# BuckModuleTest.net
KiCad netlist of a schematic drawn in EAGLE
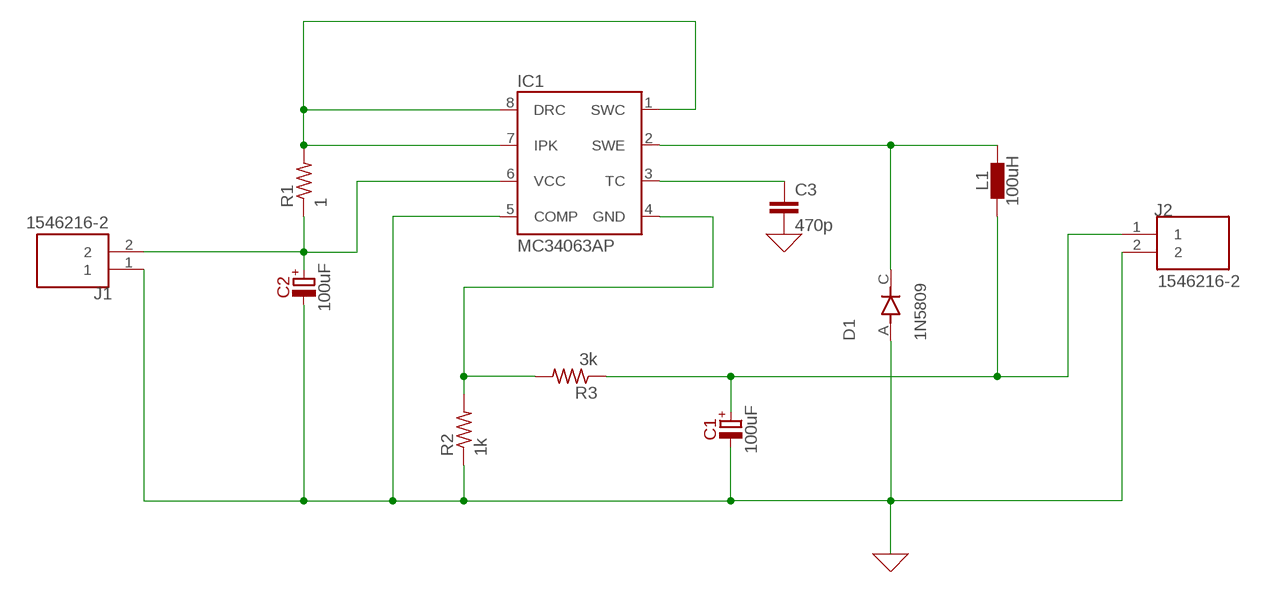
[diagram p0: schematic, sheet 1]

(export (version "E")
  (design (tool "Eeschema 10.0.6"))
  (components
    (comp (ref "C1")
      (value "100uF")
      (footprint "eagle-import:E1,5-4")
      (libsource (lib "eagle-import") (part "?1U/50V"))
    )
    (comp (ref "C2")
      (value "100uF")
      (footprint "eagle-import:E1,5-4")
      (libsource (lib "eagle-import") (part "?1U/50V"))
    )
    (comp (ref "C3")
      (value "470p")
      (footprint "eagle-import:C2.5-2")
      (libsource (lib "eagle-import") (part "C2.5/2"))
    )
    (comp (ref "D1")
      (value "1N5809")
      (footprint "eagle-import:DIOAD1060W80L520D270")
      (fields (field (name "MF") "ON Semiconductor") (field (name "MP") "1N4007"))
      (libsource (lib "eagle-import") (part "1N4007"))
    )
    (comp (ref "IC1")
      (value "MC34063AP")
      (footprint "eagle-import:DIL-08")
      (fields (field (name "MF") "Texas Instruments") (field (name "MP") "MC34063A"))
      (libsource (lib "eagle-import") (part "MC34063AP"))
    )
    (comp (ref "J1")
      (value "1546216-2")
      (footprint "eagle-import:TE_1546216-2")
      (fields (field (name "MF") "TE Connectivity"))
      (libsource (lib "eagle-import") (part "1546216-2"))
    )
    (comp (ref "J2")
      (value "1546216-2")
      (footprint "eagle-import:TE_1546216-2")
      (fields (field (name "MF") "TE Connectivity"))
      (libsource (lib "eagle-import") (part "1546216-2"))
    )
    (comp (ref "L1")
      (value "100uH")
      (footprint "eagle-import:L_NR80XX")
      (libsource (lib "eagle-import") (part "INDUCTOR-NR80XX"))
    )
    (comp (ref "R1")
      (value "1")
      (footprint "eagle-import:0207_12")
      (libsource (lib "eagle-import") (part "R-US_0207/12"))
    )
    (comp (ref "R2")
      (value "1k")
      (footprint "eagle-import:0207_12")
      (libsource (lib "eagle-import") (part "R-US_0207/12"))
    )
    (comp (ref "R3")
      (value "3k")
      (footprint "eagle-import:0207_12")
      (libsource (lib "eagle-import") (part "R-US_0207/12"))
    )
  )
  (nets
    (net (code "1") (name "GND") (class "Default")
      (node (ref "C1") (pin "-") (pinfunction "-_-") (pintype "passive"))
      (node (ref "C2") (pin "-") (pinfunction "-_-") (pintype "passive"))
      (node (ref "C3") (pin "2") (pinfunction "2_2") (pintype "passive"))
      (node (ref "D1") (pin "A") (pinfunction "A_A") (pintype "passive"))
      (node (ref "IC1") (pin "5") (pinfunction "COMP_5") (pintype "input"))
      (node (ref "J1") (pin "1") (pinfunction "1_1") (pintype "passive"))
      (node (ref "J2") (pin "2") (pinfunction "2_2") (pintype "passive"))
      (node (ref "R2") (pin "1") (pinfunction "1_1") (pintype "passive"))
    )
    (net (code "2") (name "Net-(C1-Pad+)") (class "Default")
      (node (ref "C1") (pin "+") (pinfunction "+_+") (pintype "passive"))
      (node (ref "J2") (pin "1") (pinfunction "1_1") (pintype "passive"))
      (node (ref "L1") (pin "1") (pinfunction "1_1") (pintype "passive"))
      (node (ref "R3") (pin "1") (pinfunction "1_1") (pintype "passive"))
    )
    (net (code "3") (name "Net-(IC1-DRC)") (class "Default")
      (node (ref "IC1") (pin "1") (pinfunction "SWC_1") (pintype "bidirectional"))
      (node (ref "IC1") (pin "7") (pinfunction "IPK_7") (pintype "input"))
      (node (ref "IC1") (pin "8") (pinfunction "DRC_8") (pintype "input"))
      (node (ref "R1") (pin "2") (pinfunction "2_2") (pintype "passive"))
    )
    (net (code "4") (name "Net-(IC1-GND)") (class "Default")
      (node (ref "IC1") (pin "4") (pinfunction "GND_4") (pintype "power_in"))
      (node (ref "R2") (pin "2") (pinfunction "2_2") (pintype "passive"))
      (node (ref "R3") (pin "2") (pinfunction "2_2") (pintype "passive"))
    )
    (net (code "5") (name "Net-(IC1-SWE)") (class "Default")
      (node (ref "D1") (pin "C") (pinfunction "C_C") (pintype "passive"))
      (node (ref "IC1") (pin "2") (pinfunction "SWE_2") (pintype "bidirectional"))
      (node (ref "L1") (pin "2") (pinfunction "2_2") (pintype "passive"))
    )
    (net (code "6") (name "Net-(IC1-TC)") (class "Default")
      (node (ref "C3") (pin "1") (pinfunction "1_1") (pintype "passive"))
      (node (ref "IC1") (pin "3") (pinfunction "TC_3") (pintype "passive"))
    )
    (net (code "7") (name "Net-(IC1-VCC)") (class "Default")
      (node (ref "C2") (pin "+") (pinfunction "+_+") (pintype "passive"))
      (node (ref "IC1") (pin "6") (pinfunction "VCC_6") (pintype "power_in"))
      (node (ref "J1") (pin "2") (pinfunction "2_2") (pintype "passive"))
      (node (ref "R1") (pin "1") (pinfunction "1_1") (pintype "passive"))
    )
  )
)
